# Example.net
KiCad netlist of a schematic drawn in EAGLE
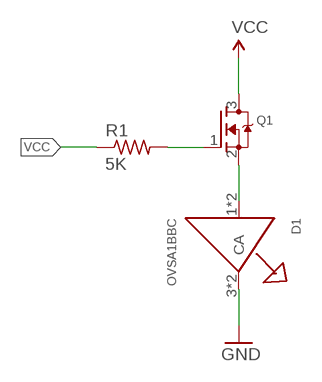
[diagram p0: schematic, sheet 1]

(export (version "E")
  (design (tool "Eeschema 10.0.6"))
  (components
    (comp (ref "D1")
      (value "OVSA1BBC")
      (footprint "eagle-import:4-PLCC")
      (libsource (lib "eagle-import") (part "OVSA1BBC"))
    )
    (comp (ref "Q1")
      (value "MOSFET-NREFLOW")
      (footprint "eagle-import:SOT23")
      (libsource (lib "eagle-import") (part "MOSFET-NREFLOW"))
    )
    (comp (ref "R1")
      (value "5K")
      (footprint "eagle-import:M0805")
      (libsource (lib "eagle-import") (part "R-US_M0805"))
    )
  )
  (nets
    (net (code "1") (name "GND") (class "Default")
      (node (ref "D1") (pin "3") (pinfunction "C_3") (pintype "bidirectional"))
      (node (ref "D1") (pin "4") (pinfunction "C_4") (pintype "bidirectional"))
    )
    (net (code "2") (name "Net-(Q1-G)") (class "Default")
      (node (ref "Q1") (pin "1") (pinfunction "G_1") (pintype "bidirectional"))
      (node (ref "R1") (pin "2") (pinfunction "2_2") (pintype "passive"))
    )
    (net (code "3") (name "Net-(Q1-S)") (class "Default")
      (node (ref "D1") (pin "1") (pinfunction "A_1") (pintype "bidirectional"))
      (node (ref "D1") (pin "2") (pinfunction "A_2") (pintype "bidirectional"))
      (node (ref "Q1") (pin "2") (pinfunction "S_2") (pintype "bidirectional"))
    )
    (net (code "4") (name "VCC") (class "Default")
      (node (ref "Q1") (pin "3") (pinfunction "D_3") (pintype "bidirectional"))
      (node (ref "R1") (pin "1") (pinfunction "1_1") (pintype "passive"))
    )
  )
)
